# SheetCopied.net
KiCad netlist of a schematic drawn in Altium Designer
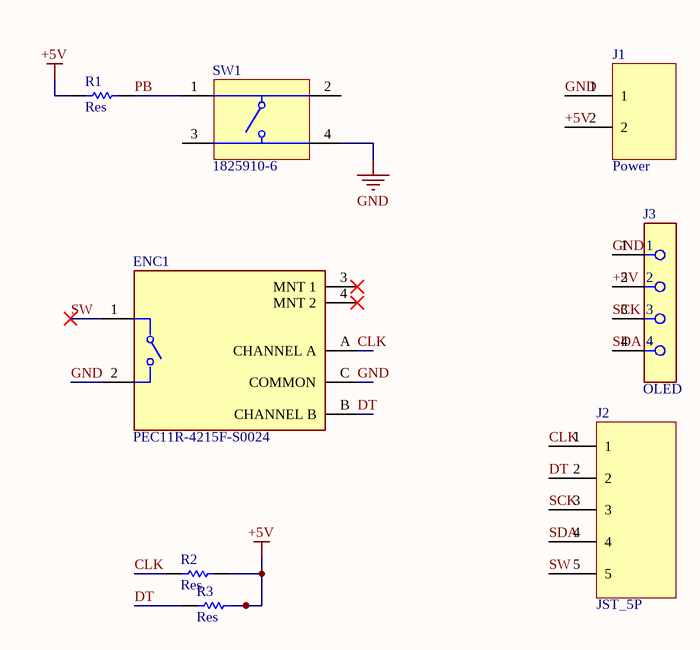
[diagram p0: SheetCopied.SchDoc]

(export (version "E")
  (design (tool "Eeschema 10.0.6"))
  (components
    (comp (ref "ENC1")
      (value "PEC11R-4215F-S0024")
      (footprint "FP-PEC11R-4215F-S0024-MFG")
      (description "ROTARY ENCODER MECHANICAL 24PPR")
      (libsource (lib "Altium Content Vault") (part "5f1dd25a4c49fa66e7eeb899730fe11"))
    )
    (comp (ref "J1") (value "Power") (footprint "JST_2P") (libsource (lib "Schlib") (part "JST_2P")))
    (comp (ref "J2") (value "JST_5P") (footprint "JST_5P") (libsource (lib "Schlib") (part "JST_5P")))
    (comp (ref "J3")
      (value "OLED")
      (footprint "FP-643416-1-MFG")
      (description "CONN HDR 4POS 0.25 TIN PCB")
      (fields
        (field (name "OCTOPART") "https://octopart.com/643416-1-te+connectivity-39538283")
        (field (name "MANUFACTURER PART NUMBER") "643416-1")
      )
      (libsource (lib "Altium Content Vault") (part "56792406a6bd5c25e158f553ecd1aa7"))
    )
    (comp (ref "R1")
      (value "Res")
      (footprint "RESC2013X60X40ML20T25")
      (fields (field (name "PART NUMBER") "ERA6AEB332V") (field (name "MANUFACTURER") "Panasonic"))
      (libsource (lib "Altium Content Vault") (part "RES"))
    )
    (comp (ref "R2")
      (value "Res")
      (footprint "RESC2013X60X40ML20T25")
      (fields (field (name "PART NUMBER") "ERA6AEB332V") (field (name "MANUFACTURER") "Panasonic"))
      (libsource (lib "Altium Content Vault") (part "RES"))
    )
    (comp (ref "R3")
      (value "Res")
      (footprint "RESC2013X60X40ML20T25")
      (fields (field (name "PART NUMBER") "ERA6AEB332V") (field (name "MANUFACTURER") "Panasonic"))
      (libsource (lib "Altium Content Vault") (part "RES"))
    )
    (comp (ref "SW1")
      (value "1825910-6")
      (footprint "TECO-1825910-6_V")
      (description "Tact Switch, SPST-NO, 0.05 A, -35 to 85 degC, 4-Pin THD, RoHS, Bulk")
      (fields (field (name "MANUFACTURER") "TE Connectivity"))
      (libsource (lib "Altium Content Vault") (part "SW-SPST-4_A"))
    )
  )
  (nets
    (net (code "1") (name "+5V") (class "Default")
      (node (ref "J1") (pin "2") (pinfunction "2_2") (pintype "passive"))
      (node (ref "J3") (pin "2") (pinfunction "2_2") (pintype "passive"))
      (node (ref "R1") (pin "1") (pinfunction "1_1") (pintype "passive"))
      (node (ref "R2") (pin "2") (pinfunction "2_2") (pintype "passive"))
      (node (ref "R3") (pin "2") (pinfunction "2_2") (pintype "passive"))
    )
    (net (code "2") (name "/CLK") (class "Default")
      (node (ref "ENC1") (pin "A") (pinfunction "CHANNEL_A_A") (pintype "passive"))
      (node (ref "J2") (pin "1") (pinfunction "1_1") (pintype "power_in"))
      (node (ref "R2") (pin "1") (pinfunction "1_1") (pintype "passive"))
    )
    (net (code "3") (name "/DT") (class "Default")
      (node (ref "ENC1") (pin "B") (pinfunction "CHANNEL_B_B") (pintype "passive"))
      (node (ref "J2") (pin "2") (pinfunction "2_2") (pintype "power_in"))
      (node (ref "R3") (pin "1") (pinfunction "1_1") (pintype "passive"))
    )
    (net (code "4") (name "/PB") (class "Default")
      (node (ref "R1") (pin "2") (pinfunction "2_2") (pintype "passive"))
      (node (ref "SW1") (pin "1") (pinfunction "1_1") (pintype "passive"))
    )
    (net (code "5") (name "/SCK") (class "Default")
      (node (ref "J2") (pin "3") (pinfunction "3_3") (pintype "passive"))
      (node (ref "J3") (pin "3") (pinfunction "3_3") (pintype "passive"))
    )
    (net (code "6") (name "/SDA") (class "Default")
      (node (ref "J2") (pin "4") (pinfunction "4_4") (pintype "passive"))
      (node (ref "J3") (pin "4") (pinfunction "4_4") (pintype "passive"))
    )
    (net (code "7") (name "/SW") (class "Default")
      (node (ref "ENC1") (pin "1") (pinfunction "1_1") (pintype "passive"))
      (node (ref "J2") (pin "5") (pinfunction "5_5") (pintype "passive"))
    )
    (net (code "8") (name "GND") (class "Default")
      (node (ref "ENC1") (pin "2") (pinfunction "2_2") (pintype "passive"))
      (node (ref "ENC1") (pin "C") (pinfunction "COMMON_C") (pintype "passive"))
      (node (ref "J1") (pin "1") (pinfunction "1_1") (pintype "passive"))
      (node (ref "J3") (pin "1") (pinfunction "1_1") (pintype "passive"))
      (node (ref "SW1") (pin "4") (pinfunction "4_4") (pintype "passive"))
    )
    (net (code "9") (name "unconnected-(ENC1-MNT_1-Pad3)") (class "Default")
      (node (ref "ENC1") (pin "3") (pinfunction "MNT_1_3") (pintype "passive+no_connect"))
    )
    (net (code "10") (name "unconnected-(ENC1-MNT_2-Pad4)") (class "Default")
      (node (ref "ENC1") (pin "4") (pinfunction "MNT_2_4") (pintype "passive+no_connect"))
    )
    (net (code "11") (name "unconnected-(SW1-Pad2)") (class "Default")
      (node (ref "SW1") (pin "2") (pinfunction "2_2") (pintype "passive"))
    )
    (net (code "12") (name "unconnected-(SW1-Pad3)") (class "Default")
      (node (ref "SW1") (pin "3") (pinfunction "3_3") (pintype "passive"))
    )
  )
)
